# notes1a.net
KiCad netlist of a schematic drawn in EAGLE
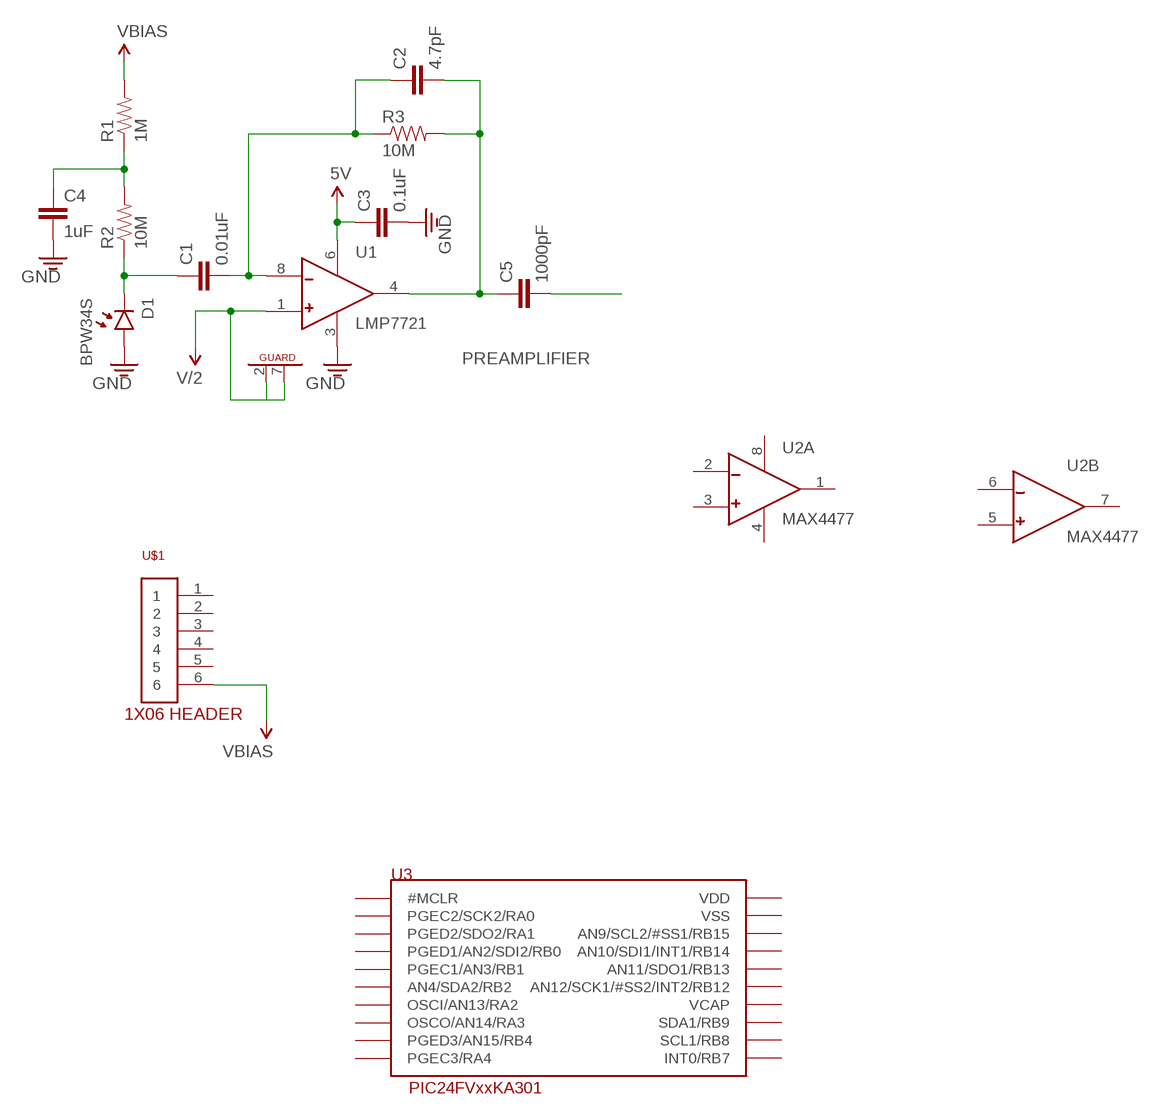
[diagram p0: schematic, sheet 1]

(export (version "E")
  (design (tool "Eeschema 10.0.6"))
  (components
    (comp (ref "C1")
      (value "0.01uF")
      (footprint "eagle-import:0603")
      (libsource (lib "eagle-import") (part "CAP0603"))
    )
    (comp (ref "C2")
      (value "4.7pF")
      (footprint "eagle-import:0603")
      (libsource (lib "eagle-import") (part "CAP0603"))
    )
    (comp (ref "C3")
      (value "0.1uF")
      (footprint "eagle-import:0603")
      (libsource (lib "eagle-import") (part "CAP0603"))
    )
    (comp (ref "C4")
      (value "1uF")
      (footprint "eagle-import:0603")
      (libsource (lib "eagle-import") (part "CAP0603"))
    )
    (comp (ref "C5")
      (value "1000pF")
      (footprint "eagle-import:0603")
      (libsource (lib "eagle-import") (part "CAP0603"))
    )
    (comp (ref "D1")
      (value "BPW34S")
      (footprint "eagle-import:BPW34S-SIDEMOUNT")
      (libsource (lib "eagle-import") (part "PHOTODIODE"))
    )
    (comp (ref "R1")
      (value "1M")
      (footprint "eagle-import:0603")
      (libsource (lib "eagle-import") (part "RESISTOR0603"))
    )
    (comp (ref "R2")
      (value "10M")
      (footprint "eagle-import:0603")
      (libsource (lib "eagle-import") (part "RESISTOR0603"))
    )
    (comp (ref "R3")
      (value "10M")
      (footprint "eagle-import:0603")
      (libsource (lib "eagle-import") (part "RESISTOR0603"))
    )
    (comp (ref "U$1")
      (value "1X06")
      (footprint "eagle-import:1X06")
      (libsource (lib "eagle-import") (part "1X06"))
    )
    (comp (ref "U1")
      (value "LMP7721")
      (footprint "eagle-import:SOIC-8")
      (libsource (lib "eagle-import") (part "OPAMP-LMP7721"))
    )
    (comp (ref "U2")
      (value "MAX4477")
      (footprint "eagle-import:SOIC-8")
      (libsource (lib "eagle-import") (part "OPAMP-MAX4477"))
    )
    (comp (ref "U3")
      (value "PIC24FVXXKA301")
      (footprint "eagle-import:SOIC-20")
      (libsource (lib "eagle-import") (part "PIC24FVXXKA301"))
    )
  )
  (nets
    (net (code "1") (name "5V") (class "Default")
      (node (ref "C3") (pin "1") (pinfunction "1_1") (pintype "passive"))
      (node (ref "U1") (pin "6") (pinfunction "VCC_6") (pintype "bidirectional"))
    )
    (net (code "2") (name "GND") (class "Default")
      (node (ref "C3") (pin "2") (pinfunction "2_2") (pintype "passive"))
      (node (ref "C4") (pin "2") (pinfunction "2_2") (pintype "passive"))
      (node (ref "D1") (pin "A") (pinfunction "ANODE_A") (pintype "bidirectional"))
      (node (ref "U1") (pin "3") (pinfunction "GND_3") (pintype "bidirectional"))
    )
    (net (code "3") (name "Net-(C4-Pad1)") (class "Default")
      (node (ref "C4") (pin "1") (pinfunction "1_1") (pintype "passive"))
      (node (ref "R1") (pin "1") (pinfunction "1_1") (pintype "passive"))
      (node (ref "R2") (pin "2") (pinfunction "2_2") (pintype "passive"))
    )
    (net (code "4") (name "Net-(D1-CATHODE)") (class "Default")
      (node (ref "C1") (pin "1") (pinfunction "1_1") (pintype "passive"))
      (node (ref "D1") (pin "C") (pinfunction "CATHODE_C") (pintype "bidirectional"))
      (node (ref "R2") (pin "1") (pinfunction "1_1") (pintype "passive"))
    )
    (net (code "5") (name "Net-(U1--)") (class "Default")
      (node (ref "C1") (pin "2") (pinfunction "2_2") (pintype "passive"))
      (node (ref "C2") (pin "1") (pinfunction "1_1") (pintype "passive"))
      (node (ref "R3") (pin "1") (pinfunction "1_1") (pintype "passive"))
      (node (ref "U1") (pin "8") (pinfunction "-_8") (pintype "bidirectional"))
    )
    (net (code "6") (name "Net-(U1-OUT)") (class "Default")
      (node (ref "C2") (pin "2") (pinfunction "2_2") (pintype "passive"))
      (node (ref "C5") (pin "1") (pinfunction "1_1") (pintype "passive"))
      (node (ref "R3") (pin "2") (pinfunction "2_2") (pintype "passive"))
      (node (ref "U1") (pin "4") (pinfunction "OUT_4") (pintype "bidirectional"))
    )
    (net (code "7") (name "VBIAS") (class "Default")
      (node (ref "R1") (pin "2") (pinfunction "2_2") (pintype "passive"))
      (node (ref "U$1") (pin "6") (pinfunction "6_6") (pintype "bidirectional"))
    )
    (net (code "8") (name "V{slash}2") (class "Default")
      (node (ref "U1") (pin "1") (pinfunction "+_1") (pintype "bidirectional"))
      (node (ref "U1") (pin "2") (pinfunction "G1_2") (pintype "bidirectional"))
      (node (ref "U1") (pin "7") (pinfunction "G2_7") (pintype "bidirectional"))
    )
    (net (code "9") (name "unconnected-(C5-Pad2)") (class "Default")
      (node (ref "C5") (pin "2") (pinfunction "2_2") (pintype "passive"))
    )
    (net (code "10") (name "unconnected-(U$1-Pad1)") (class "Default")
      (node (ref "U$1") (pin "1") (pinfunction "1_1") (pintype "bidirectional"))
    )
    (net (code "11") (name "unconnected-(U$1-Pad2)") (class "Default")
      (node (ref "U$1") (pin "2") (pinfunction "2_2") (pintype "bidirectional"))
    )
    (net (code "12") (name "unconnected-(U$1-Pad3)") (class "Default")
      (node (ref "U$1") (pin "3") (pinfunction "3_3") (pintype "bidirectional"))
    )
    (net (code "13") (name "unconnected-(U$1-Pad4)") (class "Default")
      (node (ref "U$1") (pin "4") (pinfunction "4_4") (pintype "bidirectional"))
    )
    (net (code "14") (name "unconnected-(U$1-Pad5)") (class "Default")
      (node (ref "U$1") (pin "5") (pinfunction "5_5") (pintype "bidirectional"))
    )
    (net (code "15") (name "unconnected-(U2A-+-Pad3)") (class "Default")
      (node (ref "U2") (pin "3") (pinfunction "+_3") (pintype "bidirectional"))
    )
    (net (code "16") (name "unconnected-(U2A---Pad2)") (class "Default")
      (node (ref "U2") (pin "2") (pinfunction "-_2") (pintype "bidirectional"))
    )
    (net (code "17") (name "unconnected-(U2A-OUT-Pad1)") (class "Default")
      (node (ref "U2") (pin "1") (pinfunction "OUT_1") (pintype "bidirectional"))
    )
    (net (code "18") (name "unconnected-(U2A-V+-Pad8)") (class "Default")
      (node (ref "U2") (pin "8") (pinfunction "V+_8") (pintype "bidirectional"))
    )
    (net (code "19") (name "unconnected-(U2A-V--Pad4)") (class "Default")
      (node (ref "U2") (pin "4") (pinfunction "V-_4") (pintype "bidirectional"))
    )
    (net (code "20") (name "unconnected-(U2B-+-Pad5)") (class "Default")
      (node (ref "U2") (pin "5") (pinfunction "+_5") (pintype "bidirectional"))
    )
    (net (code "21") (name "unconnected-(U2B---Pad6)") (class "Default")
      (node (ref "U2") (pin "6") (pinfunction "-_6") (pintype "bidirectional"))
    )
    (net (code "22") (name "unconnected-(U2B-OUT-Pad7)") (class "Default")
      (node (ref "U2") (pin "7") (pinfunction "OUT_7") (pintype "bidirectional"))
    )
    (net (code "23") (name "unconnected-(U3-#MCLR-Pad1)") (class "Default")
      (node (ref "U3") (pin "1") (pinfunction "#MCLR_1") (pintype "bidirectional"))
    )
    (net (code "24") (name "unconnected-(U3-AN4{slash}SDA2{slash}RB2-Pad6)") (class "Default")
      (node (ref "U3") (pin "6") (pinfunction "AN4/SDA2/RB2_6") (pintype "bidirectional"))
    )
    (net (code "25") (name "unconnected-(U3-AN9{slash}SCL2{slash}#SS1{slash}RB15-Pad18)") (class "Default")
      (node (ref "U3") (pin "18") (pinfunction "AN9/SCL2/#SS1/RB15_18") (pintype "bidirectional"))
    )
    (net (code "26") (name "unconnected-(U3-AN10{slash}SDI1{slash}INT1{slash}RB14-Pad17)") (class "Default")
      (node (ref "U3") (pin "17") (pinfunction "AN10/SDI1/INT1/RB14_17") (pintype "bidirectional"))
    )
    (net (code "27") (name "unconnected-(U3-AN11{slash}SDO1{slash}RB13-Pad16)") (class "Default")
      (node (ref "U3") (pin "16") (pinfunction "AN11/SDO1/RB13_16") (pintype "bidirectional"))
    )
    (net (code "28") (name "unconnected-(U3-AN12{slash}SCK1{slash}#SS2{slash}INT2{slash}RB12-Pad15)") (class "Default")
      (node (ref "U3") (pin "15") (pinfunction "AN12/SCK1/#SS2/INT2/RB12_15") (pintype "bidirectional"))
    )
    (net (code "29") (name "unconnected-(U3-INT0{slash}RB7-Pad11)") (class "Default")
      (node (ref "U3") (pin "11") (pinfunction "INT0/RB7_11") (pintype "bidirectional"))
    )
    (net (code "30") (name "unconnected-(U3-OSCI{slash}AN13{slash}RA2-Pad7)") (class "Default")
      (node (ref "U3") (pin "7") (pinfunction "OSCI/AN13/RA2_7") (pintype "bidirectional"))
    )
    (net (code "31") (name "unconnected-(U3-OSCO{slash}AN14{slash}RA3-Pad8)") (class "Default")
      (node (ref "U3") (pin "8") (pinfunction "OSCO/AN14/RA3_8") (pintype "bidirectional"))
    )
    (net (code "32") (name "unconnected-(U3-PGEC1{slash}AN3{slash}RB1-Pad5)") (class "Default")
      (node (ref "U3") (pin "5") (pinfunction "PGEC1/AN3/RB1_5") (pintype "bidirectional"))
    )
    (net (code "33") (name "unconnected-(U3-PGEC2{slash}SCK2{slash}RA0-Pad2)") (class "Default")
      (node (ref "U3") (pin "2") (pinfunction "PGEC2/SCK2/RA0_2") (pintype "bidirectional"))
    )
    (net (code "34") (name "unconnected-(U3-PGEC3{slash}RA4-Pad10)") (class "Default")
      (node (ref "U3") (pin "10") (pinfunction "PGEC3/RA4_10") (pintype "bidirectional"))
    )
    (net (code "35") (name "unconnected-(U3-PGED1{slash}AN2{slash}SDI2{slash}RB0-Pad4)") (class "Default")
      (node (ref "U3") (pin "4") (pinfunction "PGED1/AN2/SDI2/RB0_4") (pintype "bidirectional"))
    )
    (net (code "36") (name "unconnected-(U3-PGED2{slash}SDO2{slash}RA1-Pad3)") (class "Default")
      (node (ref "U3") (pin "3") (pinfunction "PGED2/SDO2/RA1_3") (pintype "bidirectional"))
    )
    (net (code "37") (name "unconnected-(U3-PGED3{slash}AN15{slash}RB4-Pad9)") (class "Default")
      (node (ref "U3") (pin "9") (pinfunction "PGED3/AN15/RB4_9") (pintype "bidirectional"))
    )
    (net (code "38") (name "unconnected-(U3-SCL1{slash}RB8-Pad12)") (class "Default")
      (node (ref "U3") (pin "12") (pinfunction "SCL1/RB8_12") (pintype "bidirectional"))
    )
    (net (code "39") (name "unconnected-(U3-SDA1{slash}RB9-Pad13)") (class "Default")
      (node (ref "U3") (pin "13") (pinfunction "SDA1/RB9_13") (pintype "bidirectional"))
    )
    (net (code "40") (name "unconnected-(U3-VCAP-Pad14)") (class "Default")
      (node (ref "U3") (pin "14") (pinfunction "VCAP_14") (pintype "bidirectional"))
    )
    (net (code "41") (name "unconnected-(U3-VDD-Pad20)") (class "Default")
      (node (ref "U3") (pin "20") (pinfunction "VDD_20") (pintype "bidirectional"))
    )
    (net (code "42") (name "unconnected-(U3-VSS-Pad19)") (class "Default")
      (node (ref "U3") (pin "19") (pinfunction "VSS_19") (pintype "bidirectional"))
    )
  )
)
